# Master_MCU.net
KiCad netlist of a schematic drawn in Altium Designer
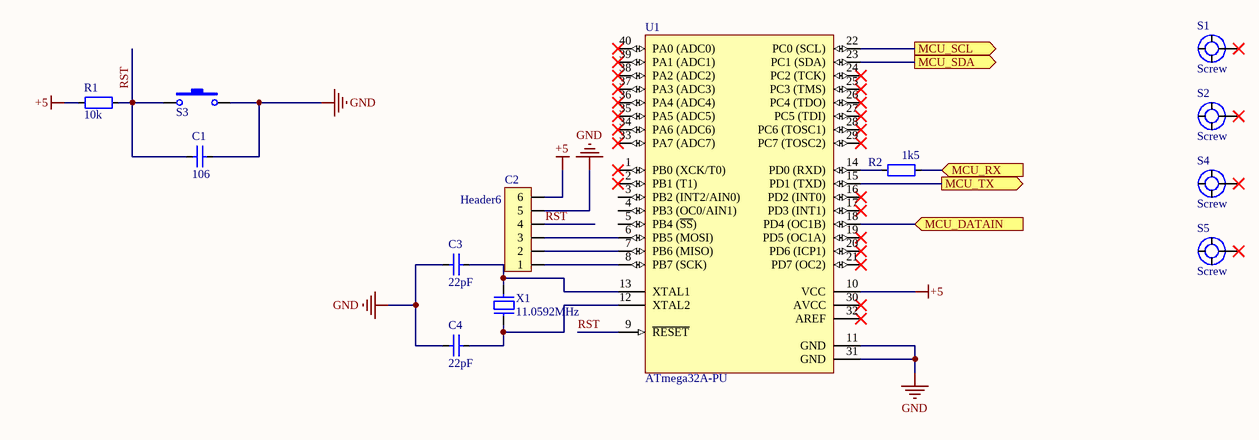
[diagram p0: Master_MCU.SchDoc]

(export (version "E")
  (design (tool "Eeschema 10.0.6"))
  (components
    (comp (ref "C1")
      (value "106")
      (footprint "CAP_0805")
      (description "Capacitor")
      (fields (field (name "PUBLISHER") "Altium Limited"))
      (libsource (lib "My Library") (part "CapSMD"))
    )
    (comp (ref "C2")
      (value "Header6")
      (footprint "JP6H")
      (description "Header IDC, 6 x 1 Pin Vertical 2.54mm Pitch (Non-Boxed, Male)")
      (fields
        (field (name "MANUFACTURER") "Würth Elektronik eiSos GmbH")
        (field (name "PARTNO") "613002143121")
        (field (name "CREATED BY") "Karrer Zheng")
      )
      (libsource (lib "My Library") (part "Header6"))
    )
    (comp (ref "C3")
      (value "22pF")
      (footprint "CAP_0805")
      (description "Capacitor")
      (fields (field (name "PUBLISHER") "Altium Limited"))
      (libsource (lib "My Library") (part "CapSMD"))
    )
    (comp (ref "C4")
      (value "22pF")
      (footprint "CAP_0805")
      (description "Capacitor")
      (fields (field (name "PUBLISHER") "Altium Limited"))
      (libsource (lib "My Library") (part "CapSMD"))
    )
    (comp (ref "R1")
      (value "10k")
      (footprint "RES-SMD-0805")
      (description "Resistor")
      (fields
        (field (name "MANUFACTURER") "Generic Components")
        (field (name "PUBLISHER") "Altium Hobart Technology Centre")
      )
      (libsource (lib "My Library") (part "Resistor - SMD"))
    )
    (comp (ref "R2")
      (value "1k5")
      (footprint "RES-SMD-0805")
      (description "Resistor")
      (fields
        (field (name "MANUFACTURER") "Generic Components")
        (field (name "PUBLISHER") "Altium Hobart Technology Centre")
      )
      (libsource (lib "My Library") (part "Resistor - SMD"))
    )
    (comp (ref "S1")
      (value "Screw")
      (footprint "LPON_OTHER:Screw 3 small")
      (libsource (lib "lpson") (part "Screw"))
    )
    (comp (ref "S2") (value "Screw") (footprint "Screw 3 small") (libsource (lib "lpson") (part "Screw")))
    (comp (ref "S3")
      (value "SW-SMD")
      (footprint "SW 3x2x4")
      (description "Switch")
      (fields (field (name "PUBLISHER") "Altium Limited"))
      (libsource (lib "My Library") (part "SW-SMD"))
    )
    (comp (ref "S4") (value "Screw") (footprint "Screw 3 small") (libsource (lib "lpson") (part "Screw")))
    (comp (ref "S5")
      (value "Screw")
      (footprint "LPON_OTHER:Screw 3 small")
      (libsource (lib "lpson") (part "Screw"))
    )
    (comp (ref "U1")
      (value "ATmega32A-PU")
      (footprint "DIP40/W0.6")
      (description "8-Bit AVR Microcontroller with 32K Bytes of In-System Programmable Flash Memory")
      (fields (field (name "PUBLISHER") "Altium Limited"))
      (libsource (lib "My Library") (part "ATmega32A-PU"))
    )
    (comp (ref "X1")
      (value "11.0592MHz")
      (footprint "XT2")
      (description "Crystal For all Crystal 2pin.")
      (libsource (lib "My Library") (part "XT2"))
    )
  )
  (nets
    (net (code "1") (name "+5") (class "Default")
      (node (ref "C2") (pin "6") (pinfunction "6_6") (pintype "passive"))
      (node (ref "R1") (pin "1") (pinfunction "1_1") (pintype "passive"))
      (node (ref "U1") (pin "10") (pinfunction "VCC_10") (pintype "power_in"))
    )
    (net (code "2") (name "/MCU_DATAIN") (class "Default")
      (node (ref "U1") (pin "18") (pinfunction "PD4_(OC1B)_18") (pintype "bidirectional"))
    )
    (net (code "3") (name "/MCU_RX") (class "Default")
      (node (ref "R2") (pin "2") (pinfunction "2_2") (pintype "passive"))
    )
    (net (code "4") (name "/MCU_SCL") (class "Default")
      (node (ref "U1") (pin "22") (pinfunction "PC0_(SCL)_22") (pintype "bidirectional"))
    )
    (net (code "5") (name "/MCU_SDA") (class "Default")
      (node (ref "U1") (pin "23") (pinfunction "PC1_(SDA)_23") (pintype "bidirectional"))
    )
    (net (code "6") (name "/MCU_TX") (class "Default")
      (node (ref "U1") (pin "15") (pinfunction "PD1_(TXD)_15") (pintype "bidirectional"))
    )
    (net (code "9") (name "/RST") (class "Default")
      (node (ref "C1") (pin "1") (pinfunction "1_1") (pintype "passive"))
      (node (ref "C2") (pin "4") (pinfunction "4_4") (pintype "passive"))
      (node (ref "R1") (pin "2") (pinfunction "2_2") (pintype "passive"))
      (node (ref "S3") (pin "1") (pinfunction "1_1") (pintype "passive"))
      (node (ref "U1") (pin "9") (pinfunction "~{RESET}_9") (pintype "input"))
    )
    (net (code "10") (name "GND") (class "Default")
      (node (ref "C1") (pin "2") (pinfunction "2_2") (pintype "passive"))
      (node (ref "C2") (pin "5") (pinfunction "5_5") (pintype "passive"))
      (node (ref "C3") (pin "1") (pinfunction "1_1") (pintype "passive"))
      (node (ref "C4") (pin "1") (pinfunction "1_1") (pintype "passive"))
      (node (ref "S3") (pin "2") (pinfunction "2_2") (pintype "passive"))
      (node (ref "U1") (pin "11") (pinfunction "GND_11") (pintype "power_in"))
      (node (ref "U1") (pin "31") (pinfunction "GND_31") (pintype "power_in"))
    )
    (net (code "11") (name "Net-(U1-PB5_(MOSI))") (class "Default")
      (node (ref "C2") (pin "3") (pinfunction "3_3") (pintype "passive"))
      (node (ref "U1") (pin "6") (pinfunction "PB5_(MOSI)_6") (pintype "bidirectional"))
    )
    (net (code "12") (name "Net-(U1-PB6_(MISO))") (class "Default")
      (node (ref "C2") (pin "2") (pinfunction "2_2") (pintype "passive"))
      (node (ref "U1") (pin "7") (pinfunction "PB6_(MISO)_7") (pintype "bidirectional"))
    )
    (net (code "13") (name "Net-(U1-PB7_(SCK))") (class "Default")
      (node (ref "C2") (pin "1") (pinfunction "1_1") (pintype "passive"))
      (node (ref "U1") (pin "8") (pinfunction "PB7_(SCK)_8") (pintype "bidirectional"))
    )
    (net (code "14") (name "Net-(U1-PD0_(RXD))") (class "Default")
      (node (ref "R2") (pin "1") (pinfunction "1_1") (pintype "passive"))
      (node (ref "U1") (pin "14") (pinfunction "PD0_(RXD)_14") (pintype "bidirectional"))
    )
    (net (code "15") (name "Net-(U1-XTAL1)") (class "Default")
      (node (ref "C3") (pin "2") (pinfunction "2_2") (pintype "passive"))
      (node (ref "U1") (pin "13") (pinfunction "XTAL1_13") (pintype "passive"))
      (node (ref "X1") (pin "2") (pinfunction "2_2") (pintype "passive"))
    )
    (net (code "16") (name "Net-(U1-XTAL2)") (class "Default")
      (node (ref "C4") (pin "2") (pinfunction "2_2") (pintype "passive"))
      (node (ref "U1") (pin "12") (pinfunction "XTAL2_12") (pintype "passive"))
      (node (ref "X1") (pin "1") (pinfunction "1_1") (pintype "passive"))
    )
    (net (code "17") (name "unconnected-(S1-Pad1)") (class "Default")
      (node (ref "S1") (pin "1") (pinfunction "1_1") (pintype "passive+no_connect"))
    )
    (net (code "18") (name "unconnected-(S2-Pad1)") (class "Default")
      (node (ref "S2") (pin "1") (pinfunction "1_1") (pintype "passive+no_connect"))
    )
    (net (code "19") (name "unconnected-(S4-Pad1)") (class "Default")
      (node (ref "S4") (pin "1") (pinfunction "1_1") (pintype "passive+no_connect"))
    )
    (net (code "20") (name "unconnected-(S5-Pad1)") (class "Default")
      (node (ref "S5") (pin "1") (pinfunction "1_1") (pintype "passive+no_connect"))
    )
    (net (code "21") (name "unconnected-(U1-AREF-Pad32)") (class "Default")
      (node (ref "U1") (pin "32") (pinfunction "AREF_32") (pintype "power_in+no_connect"))
    )
    (net (code "22") (name "unconnected-(U1-AVCC-Pad30)") (class "Default")
      (node (ref "U1") (pin "30") (pinfunction "AVCC_30") (pintype "power_in+no_connect"))
    )
    (net (code "23") (name "unconnected-(U1-PA0_(ADC0)-Pad40)") (class "Default")
      (node (ref "U1") (pin "40") (pinfunction "PA0_(ADC0)_40") (pintype "bidirectional+no_connect"))
    )
    (net (code "24") (name "unconnected-(U1-PA1_(ADC1)-Pad39)") (class "Default")
      (node (ref "U1") (pin "39") (pinfunction "PA1_(ADC1)_39") (pintype "bidirectional+no_connect"))
    )
    (net (code "25") (name "unconnected-(U1-PA2_(ADC2)-Pad38)") (class "Default")
      (node (ref "U1") (pin "38") (pinfunction "PA2_(ADC2)_38") (pintype "bidirectional+no_connect"))
    )
    (net (code "26") (name "unconnected-(U1-PA3_(ADC3)-Pad37)") (class "Default")
      (node (ref "U1") (pin "37") (pinfunction "PA3_(ADC3)_37") (pintype "bidirectional+no_connect"))
    )
    (net (code "27") (name "unconnected-(U1-PA4_(ADC4)-Pad36)") (class "Default")
      (node (ref "U1") (pin "36") (pinfunction "PA4_(ADC4)_36") (pintype "bidirectional+no_connect"))
    )
    (net (code "28") (name "unconnected-(U1-PA5_(ADC5)-Pad35)") (class "Default")
      (node (ref "U1") (pin "35") (pinfunction "PA5_(ADC5)_35") (pintype "bidirectional+no_connect"))
    )
    (net (code "29") (name "unconnected-(U1-PA6_(ADC6)-Pad34)") (class "Default")
      (node (ref "U1") (pin "34") (pinfunction "PA6_(ADC6)_34") (pintype "bidirectional+no_connect"))
    )
    (net (code "30") (name "unconnected-(U1-PA7_(ADC7)-Pad33)") (class "Default")
      (node (ref "U1") (pin "33") (pinfunction "PA7_(ADC7)_33") (pintype "bidirectional+no_connect"))
    )
    (net (code "31") (name "unconnected-(U1-PB0_(XCK{slash}T0)-Pad1)") (class "Default")
      (node (ref "U1") (pin "1") (pinfunction "PB0_(XCK/T0)_1") (pintype "bidirectional+no_connect"))
    )
    (net (code "32") (name "unconnected-(U1-PB1_(T1)-Pad2)") (class "Default")
      (node (ref "U1") (pin "2") (pinfunction "PB1_(T1)_2") (pintype "bidirectional+no_connect"))
    )
    (net (code "33") (name "unconnected-(U1-PB2_(INT2{slash}AIN0)-Pad3)") (class "Default")
      (node (ref "U1") (pin "3") (pinfunction "PB2_(INT2/AIN0)_3") (pintype "bidirectional"))
    )
    (net (code "34") (name "unconnected-(U1-PB3_(OC0{slash}AIN1)-Pad4)") (class "Default")
      (node (ref "U1") (pin "4") (pinfunction "PB3_(OC0/AIN1)_4") (pintype "bidirectional"))
    )
    (net (code "35") (name "unconnected-(U1-PB4_(~{SS})-Pad5)") (class "Default")
      (node (ref "U1") (pin "5") (pinfunction "PB4_(~{SS})_5") (pintype "bidirectional"))
    )
    (net (code "36") (name "unconnected-(U1-PC2_(TCK)-Pad24)") (class "Default")
      (node (ref "U1") (pin "24") (pinfunction "PC2_(TCK)_24") (pintype "bidirectional+no_connect"))
    )
    (net (code "37") (name "unconnected-(U1-PC3_(TMS)-Pad25)") (class "Default")
      (node (ref "U1") (pin "25") (pinfunction "PC3_(TMS)_25") (pintype "bidirectional+no_connect"))
    )
    (net (code "38") (name "unconnected-(U1-PC4_(TDO)-Pad26)") (class "Default")
      (node (ref "U1") (pin "26") (pinfunction "PC4_(TDO)_26") (pintype "bidirectional+no_connect"))
    )
    (net (code "39") (name "unconnected-(U1-PC5_(TDI)-Pad27)") (class "Default")
      (node (ref "U1") (pin "27") (pinfunction "PC5_(TDI)_27") (pintype "bidirectional+no_connect"))
    )
    (net (code "40") (name "unconnected-(U1-PC6_(TOSC1)-Pad28)") (class "Default")
      (node (ref "U1") (pin "28") (pinfunction "PC6_(TOSC1)_28") (pintype "bidirectional+no_connect"))
    )
    (net (code "41") (name "unconnected-(U1-PC7_(TOSC2)-Pad29)") (class "Default")
      (node (ref "U1") (pin "29") (pinfunction "PC7_(TOSC2)_29") (pintype "bidirectional+no_connect"))
    )
    (net (code "42") (name "unconnected-(U1-PD2_(INT0)-Pad16)") (class "Default")
      (node (ref "U1") (pin "16") (pinfunction "PD2_(INT0)_16") (pintype "bidirectional+no_connect"))
    )
    (net (code "43") (name "unconnected-(U1-PD3_(INT1)-Pad17)") (class "Default")
      (node (ref "U1") (pin "17") (pinfunction "PD3_(INT1)_17") (pintype "bidirectional+no_connect"))
    )
    (net (code "44") (name "unconnected-(U1-PD5_(OC1A)-Pad19)") (class "Default")
      (node (ref "U1") (pin "19") (pinfunction "PD5_(OC1A)_19") (pintype "bidirectional+no_connect"))
    )
    (net (code "45") (name "unconnected-(U1-PD6_(ICP1)-Pad20)") (class "Default")
      (node (ref "U1") (pin "20") (pinfunction "PD6_(ICP1)_20") (pintype "bidirectional+no_connect"))
    )
    (net (code "46") (name "unconnected-(U1-PD7_(OC2)-Pad21)") (class "Default")
      (node (ref "U1") (pin "21") (pinfunction "PD7_(OC2)_21") (pintype "bidirectional+no_connect"))
    )
  )
)
